# POWER.net
KiCad netlist of a schematic drawn in Altium Designer
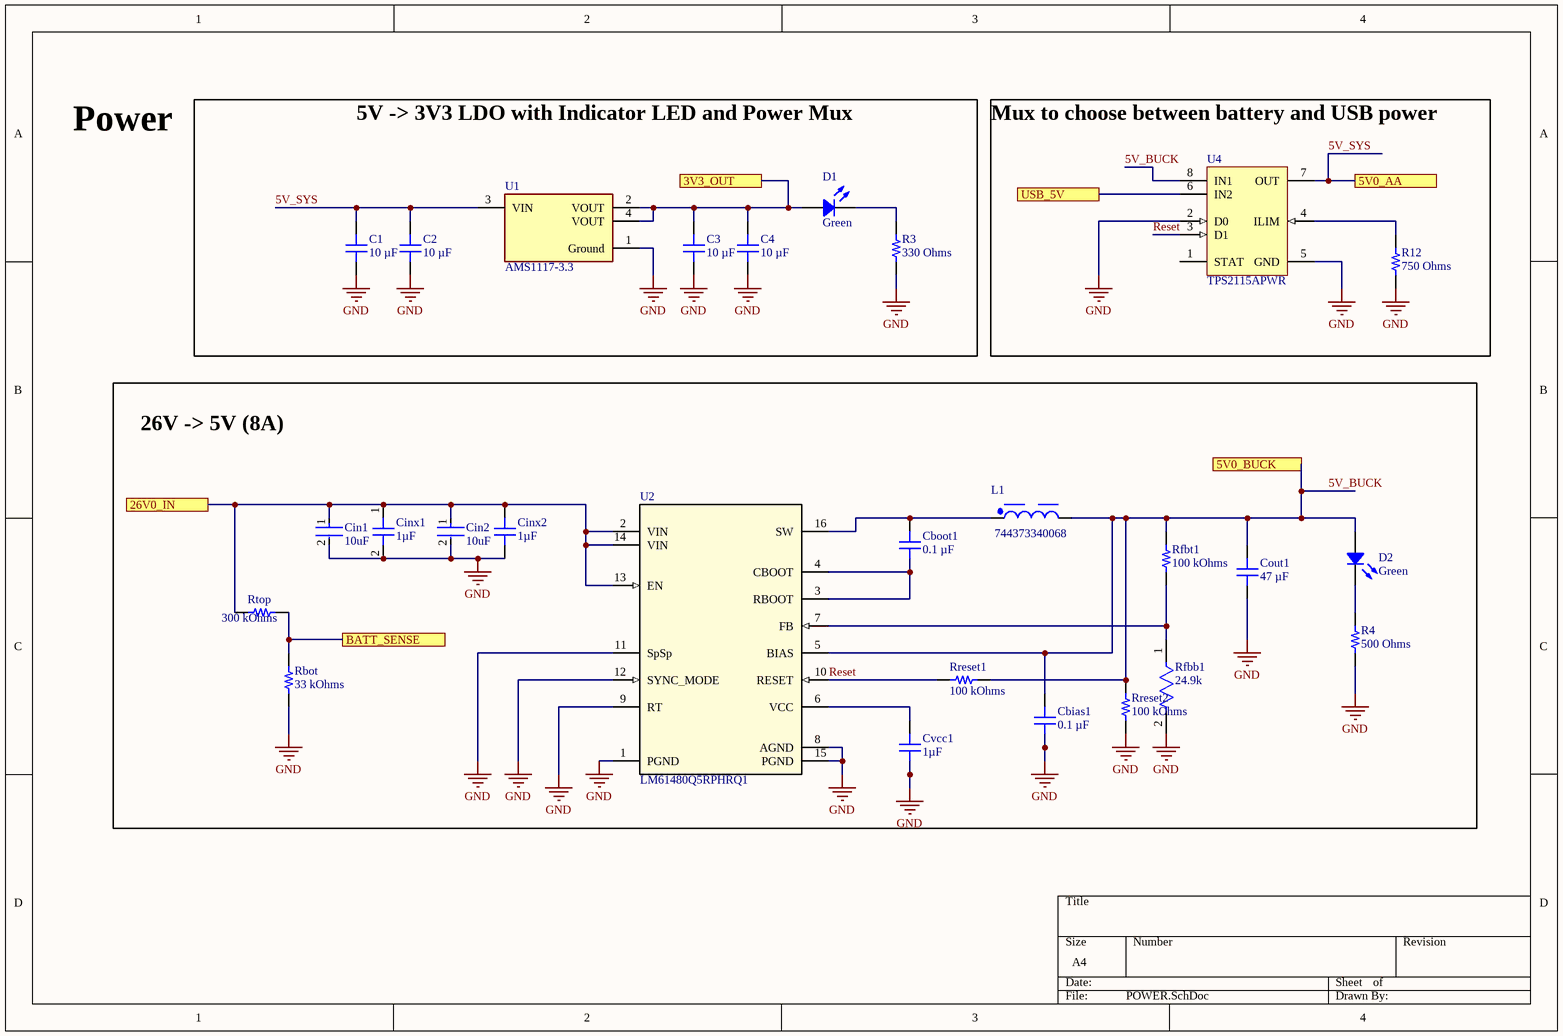
[diagram p0: POWER.SchDoc]

(export (version "E")
  (design (tool "Eeschema 10.0.6"))
  (components
    (comp (ref "C1")
      (value "10 µF")
      (footprint "CAP 0603_1608")
      (description "0603 X5R 10UF10% 16V")
      (fields (field (name "PART NUMBER") "CM105X5R106K16AT") (field (name "MANUFACTURER") "KYOCERA AVX"))
      (libsource (lib "Celestial Altium Library - altium_library") (part "Capacitor"))
    )
    (comp (ref "C2")
      (value "10 µF")
      (footprint "CAP 0603_1608")
      (description "0603 X5R 10UF10% 16V")
      (fields (field (name "PART NUMBER") "CM105X5R106K16AT") (field (name "MANUFACTURER") "KYOCERA AVX"))
      (libsource (lib "Celestial Altium Library - altium_library") (part "Capacitor"))
    )
    (comp (ref "C3")
      (value "10 µF")
      (footprint "CAP 0603_1608")
      (description "0603 X5R 10UF10% 16V")
      (fields (field (name "PART NUMBER") "CM105X5R106K16AT") (field (name "MANUFACTURER") "KYOCERA AVX"))
      (libsource (lib "Celestial Altium Library - altium_library") (part "Capacitor"))
    )
    (comp (ref "C4")
      (value "10 µF")
      (footprint "CAP 0603_1608")
      (description "0603 X5R 10UF10% 16V")
      (fields (field (name "PART NUMBER") "CM105X5R106K16AT") (field (name "MANUFACTURER") "KYOCERA AVX"))
      (libsource (lib "Celestial Altium Library - altium_library") (part "Capacitor"))
    )
    (comp (ref "Cbias1")
      (value "0.1 µF")
      (footprint "CAP 0603_1608")
      (description "CAP CER 0.1UF 50V X7R 0603")
      (fields
        (field (name "PART NUMBER") "C0603C104K5RAC7411")
        (field (name "CAPACITANCE") "0.1 µF")
        (field (name "MANUFACTURER") "KEMET")
      )
      (libsource (lib "Celestial Altium Library - altium_library") (part "Capacitor"))
    )
    (comp (ref "Cboot1")
      (value "0.1 µF")
      (footprint "CAP 0603_1608")
      (description "CAP CER 0.1UF 50V X7R 0603")
      (fields
        (field (name "PART NUMBER") "C0603C104K5RAC7411")
        (field (name "CAPACITANCE") "0.1 µF")
        (field (name "MANUFACTURER") "KEMET")
      )
      (libsource (lib "Celestial Altium Library - altium_library") (part "Capacitor"))
    )
    (comp (ref "Cin1")
      (value "10uF")
      (footprint "FP-GRT31C-0_2-IPC_A")
      (description "CAP CER 10UF 50V X5R 1206")
      (fields (field (name "TOLERANCE") "20%"))
      (libsource (lib "Altium Content Vault") (part "11868f565c42a9108669ba33697ecf6"))
    )
    (comp (ref "Cin2")
      (value "10uF")
      (footprint "FP-GRT31C-0_2-IPC_A")
      (description "CAP CER 10UF 50V X5R 1206")
      (fields (field (name "TOLERANCE") "20%"))
      (libsource (lib "Altium Content Vault") (part "11868f565c42a9108669ba33697ecf6"))
    )
    (comp (ref "Cinx1")
      (value "1µF")
      (footprint "CAP 0603_1608")
      (description "CAP CER 1UF 50V X5R 0603")
      (fields
        (field (name "PART NUMBER") "06035D105MAT2A")
        (field (name "CAPACITANCE") "1µF")
        (field (name "MANUFACTURER") "AVX Corporation")
      )
      (libsource (lib "") (part "Capacitor_1"))
    )
    (comp (ref "Cinx2")
      (value "1µF")
      (footprint "CAP 0603_1608")
      (description "CAP CER 1UF 50V X5R 0603")
      (fields
        (field (name "PART NUMBER") "06035D105MAT2A")
        (field (name "CAPACITANCE") "1µF")
        (field (name "MANUFACTURER") "AVX Corporation")
      )
      (libsource (lib "Celestial Altium Library - altium_library") (part "Capacitor"))
    )
    (comp (ref "Cout1")
      (value "47 µF")
      (footprint "CAP 0603_1608")
      (description "CAP CER 47UF 6.3V X5R 0603")
      (fields
        (field (name "PART NUMBER") "CL10A476MQ8QRNC")
        (field (name "CAPACITANCE") "47 µF")
        (field (name "MANUFACTURER") "Samsung Electro-Mechanics")
      )
      (libsource (lib "Celestial Altium Library - altium_library") (part "Capacitor"))
    )
    (comp (ref "Cvcc1")
      (value "1µF")
      (footprint "CAP 0603_1608")
      (description "CAP CER 1UF 50V X5R 0603")
      (fields
        (field (name "PART NUMBER") "06035D105MAT2A")
        (field (name "CAPACITANCE") "1µF")
        (field (name "MANUFACTURER") "AVX Corporation")
      )
      (libsource (lib "Celestial Altium Library - altium_library") (part "Capacitor"))
    )
    (comp (ref "D1")
      (value "Green")
      (footprint "LED 0603_1608 GREEN")
      (description "LED GREEN CLEAR 0603 SMD")
      (fields (field (name "PART NUMBER") "150060GS75003") (field (name "MANUFACTURER") "Würth Elektronik"))
      (libsource (lib "Celestial Altium Library - altium_library") (part "LED"))
    )
    (comp (ref "D2")
      (value "Green")
      (footprint "LED 0603_1608 GREEN")
      (description "LED GREEN CLEAR 0603 SMD")
      (fields (field (name "PART NUMBER") "150060GS75003") (field (name "MANUFACTURER") "Würth Elektronik"))
      (libsource (lib "Celestial Altium Library - altium_library") (part "LED"))
    )
    (comp (ref "L1")
      (value "744373340068")
      (footprint "WE-LHMI_5020")
      (description "We-lhmi Series, Shielded Wire-wound SMD Inductor 680 Nh +/-20% Wire-wound 6.8A I")
      (fields (field (name "TOLERANCE") "20%"))
      (libsource (lib "Altium Content Vault") (part "Inductor - 2"))
    )
    (comp (ref "R3")
      (value "330 Ohms")
      (footprint "RES 0603_1608")
      (description "RES 330 OHM 0.1% 1/8W 0603")
      (fields
        (field (name "PART NUMBER") "ERA-3VEB3300V")
        (field (name "MANUFACTURER") "Panasonic Electronic Components")
      )
      (libsource (lib "Celestial Altium Library - altium_library") (part "Resistor"))
    )
    (comp (ref "R4")
      (value "500 Ohms")
      (footprint "RES 1206_3216")
      (description "RES SMD 500 OHM 0.05% 0.4W 1206")
      (fields
        (field (name "PART NUMBER") "PLT1206Z5000AST5")
        (field (name "MANUFACTURER") "Vishay Thin Film")
      )
      (libsource (lib "Celestial Altium Library - altium_library") (part "Resistor"))
    )
    (comp (ref "R12")
      (value "750 Ohms")
      (footprint "RES 0603_1608")
      (description "RES SMD 750 OHM 1% 1/16W 0603")
      (fields
        (field (name "PART NUMBER") "CPF0603F750RC1")
        (field (name "MANUFACTURER") "TE Connectivity Passive Product")
      )
      (libsource (lib "Celestial Altium Library - altium_library") (part "Resistor"))
    )
    (comp (ref "Rbot")
      (value "33 kOhms")
      (footprint "YAGEO RES 0603_1608")
      (description "RES SMD 33K OHM 1% 1/10W 0603")
      (fields (field (name "PART NUMBER") "RT0603FRE0733KL") (field (name "MANUFACTURER") "Yageo"))
      (libsource (lib "Celestial Altium Library - altium_library") (part "Resistor"))
    )
    (comp (ref "Rfbb1")
      (value "24.9k")
      (footprint "FP-TFCR0603-IPC_A")
      (description "RES Thin Film,  24.9kΩ, 1%, 0.1W, 50ppm/°C, 0603")
      (libsource (lib "Altium Content Vault") (part "1029c3af85768c4190bb7ad29bc67b5"))
    )
    (comp (ref "Rfbt1")
      (value "100 kOhms")
      (footprint "RES 0603_1608")
      (description "RES 100K OHM 0.1% 1/16W 0603")
      (fields
        (field (name "PART NUMBER") "RNCS0603BKE100K")
        (field (name "MANUFACTURER") "Stackpole Electronics Inc")
      )
      (libsource (lib "Celestial Altium Library - altium_library") (part "Resistor"))
    )
    (comp (ref "Rreset1")
      (value "100 kOhms")
      (footprint "RES 0603_1608")
      (description "RES 100K OHM 0.1% 1/16W 0603")
      (fields
        (field (name "PART NUMBER") "RNCS0603BKE100K")
        (field (name "MANUFACTURER") "Stackpole Electronics Inc")
      )
      (libsource (lib "Celestial Altium Library - altium_library") (part "Resistor"))
    )
    (comp (ref "Rreset2")
      (value "100 kOhms")
      (footprint "RES 0603_1608")
      (description "RES 100K OHM 0.1% 1/16W 0603")
      (fields
        (field (name "PART NUMBER") "RNCS0603BKE100K")
        (field (name "MANUFACTURER") "Stackpole Electronics Inc")
      )
      (libsource (lib "Celestial Altium Library - altium_library") (part "Resistor"))
    )
    (comp (ref "Rtop")
      (value "300 kOhms")
      (footprint "YAGEO RES 0603_1608")
      (description "RES 300K OHM 1% 1/10W 0603")
      (fields (field (name "PART NUMBER") "RC0603FR-07300KL") (field (name "MANUFACTURER") "Yageo"))
      (libsource (lib "Celestial Altium Library - altium_library") (part "Resistor"))
    )
    (comp (ref "U1")
      (value "AMS1117-3.3")
      (footprint "FP-AMS1117-IPC_C")
      (description "LDO Voltage Regulators 1A, 3.3V")
      (fields
        (field (name "OCTOPART") "https://octopart.com/ams1117-3.3-advanced+monolithic+systems-25899300")
        (field (name "MANUFACTURER") "Advanced Monolithic Systems")
      )
      (libsource (lib "Altium Content Vault") (part "8bdbb5f8e77002000e30dd2845d0354"))
    )
    (comp (ref "U2")
      (value "LM61480Q5RPHRQ1")
      (footprint "RPH0016A")
      (description "Automotive 8A buck converter optimized for power density and low EMI 16-VQFN-HR -40 to 150")
      (fields (field (name "COPYRIGHT") "Copyright (C) 2025 Ultra Librarian. All rights reserved."))
      (libsource (lib "LM61480Q5RPHRQ1") (part "LM61480Q5RPHRQ1"))
    )
    (comp (ref "U4")
      (value "TPS2115APWR")
      (footprint "PW0008A_N")
      (fields (field (name "MANUFACTURER") "Texas Instruments"))
      (libsource (lib "Altium Content Vault") (part "TI-TPS2115APW8"))
    )
  )
  (nets
    (net (code "1") (name "/3V3_OUT") (class "Default")
      (node (ref "C3") (pin "2") (pinfunction "2_2") (pintype "passive"))
      (node (ref "C4") (pin "2") (pinfunction "2_2") (pintype "passive"))
      (node (ref "D1") (pin "1") (pinfunction "1_1") (pintype "passive"))
      (node (ref "U1") (pin "2") (pinfunction "VOUT_2") (pintype "passive"))
      (node (ref "U1") (pin "4") (pinfunction "VOUT_4") (pintype "passive"))
    )
    (net (code "2") (name "/5V_BUCK") (class "Default")
      (node (ref "Cbias1") (pin "1") (pinfunction "1_1") (pintype "passive"))
      (node (ref "Cout1") (pin "1") (pinfunction "1_1") (pintype "passive"))
      (node (ref "D2") (pin "1") (pinfunction "1_1") (pintype "passive"))
      (node (ref "L1") (pin "2") (pinfunction "2_2") (pintype "passive"))
      (node (ref "Rfbt1") (pin "1") (pinfunction "1_1") (pintype "passive"))
      (node (ref "Rreset1") (pin "2") (pinfunction "2_2") (pintype "passive"))
      (node (ref "Rreset2") (pin "1") (pinfunction "1_1") (pintype "passive"))
      (node (ref "U2") (pin "5") (pinfunction "BIAS_5") (pintype "passive"))
      (node (ref "U4") (pin "8") (pinfunction "IN1_8") (pintype "power_in"))
    )
    (net (code "3") (name "/5V_SYS") (class "Default")
      (node (ref "C1") (pin "2") (pinfunction "2_2") (pintype "passive"))
      (node (ref "C2") (pin "2") (pinfunction "2_2") (pintype "passive"))
      (node (ref "U1") (pin "3") (pinfunction "VIN_3") (pintype "power_in"))
      (node (ref "U4") (pin "7") (pinfunction "OUT_7") (pintype "power_in"))
    )
    (net (code "4") (name "/26V0_IN") (class "Default")
      (node (ref "Cin1") (pin "1") (pinfunction "1_1") (pintype "passive"))
      (node (ref "Cin2") (pin "1") (pinfunction "1_1") (pintype "passive"))
      (node (ref "Cinx1") (pin "1") (pinfunction "1_1") (pintype "passive"))
      (node (ref "Cinx2") (pin "1") (pinfunction "1_1") (pintype "passive"))
      (node (ref "Rtop") (pin "1") (pinfunction "1_1") (pintype "passive"))
      (node (ref "U2") (pin "13") (pinfunction "EN_13") (pintype "input"))
      (node (ref "U2") (pin "14") (pinfunction "VIN_14") (pintype "power_in"))
      (node (ref "U2") (pin "2") (pinfunction "VIN_2") (pintype "power_in"))
    )
    (net (code "5") (name "/BATT_SENSE") (class "Default")
      (node (ref "Rbot") (pin "1") (pinfunction "1_1") (pintype "passive"))
      (node (ref "Rtop") (pin "2") (pinfunction "2_2") (pintype "passive"))
    )
    (net (code "6") (name "/Reset") (class "Default")
      (node (ref "Rreset1") (pin "1") (pinfunction "1_1") (pintype "passive"))
      (node (ref "U2") (pin "10") (pinfunction "RESET_10") (pintype "input"))
      (node (ref "U4") (pin "3") (pinfunction "D1_3") (pintype "input"))
    )
    (net (code "7") (name "/USB_5V") (class "Default")
      (node (ref "U4") (pin "6") (pinfunction "IN2_6") (pintype "power_in"))
    )
    (net (code "8") (name "GND") (class "Default")
      (node (ref "C1") (pin "1") (pinfunction "1_1") (pintype "passive"))
      (node (ref "C2") (pin "1") (pinfunction "1_1") (pintype "passive"))
      (node (ref "C3") (pin "1") (pinfunction "1_1") (pintype "passive"))
      (node (ref "C4") (pin "1") (pinfunction "1_1") (pintype "passive"))
      (node (ref "Cbias1") (pin "2") (pinfunction "2_2") (pintype "passive"))
      (node (ref "Cin1") (pin "2") (pinfunction "2_2") (pintype "passive"))
      (node (ref "Cin2") (pin "2") (pinfunction "2_2") (pintype "passive"))
      (node (ref "Cinx1") (pin "2") (pinfunction "2_2") (pintype "passive"))
      (node (ref "Cinx2") (pin "2") (pinfunction "2_2") (pintype "passive"))
      (node (ref "Cout1") (pin "2") (pinfunction "2_2") (pintype "passive"))
      (node (ref "Cvcc1") (pin "2") (pinfunction "2_2") (pintype "passive"))
      (node (ref "R12") (pin "2") (pinfunction "2_2") (pintype "passive"))
      (node (ref "R3") (pin "1") (pinfunction "1_1") (pintype "passive"))
      (node (ref "R4") (pin "2") (pinfunction "2_2") (pintype "passive"))
      (node (ref "Rbot") (pin "2") (pinfunction "2_2") (pintype "passive"))
      (node (ref "Rfbb1") (pin "2") (pinfunction "2_2") (pintype "passive"))
      (node (ref "Rreset2") (pin "2") (pinfunction "2_2") (pintype "passive"))
      (node (ref "U1") (pin "1") (pinfunction "Ground_1") (pintype "power_in"))
      (node (ref "U2") (pin "1") (pinfunction "PGND_1") (pintype "power_in"))
      (node (ref "U2") (pin "11") (pinfunction "SpSp_11") (pintype "passive"))
      (node (ref "U2") (pin "12") (pinfunction "SYNC_MODE_12") (pintype "input"))
      (node (ref "U2") (pin "15") (pinfunction "PGND_15") (pintype "power_in"))
      (node (ref "U2") (pin "8") (pinfunction "AGND_8") (pintype "power_in"))
      (node (ref "U2") (pin "9") (pinfunction "RT_9") (pintype "passive"))
      (node (ref "U4") (pin "2") (pinfunction "D0_2") (pintype "input"))
      (node (ref "U4") (pin "5") (pinfunction "GND_5") (pintype "power_in"))
    )
    (net (code "9") (name "Net-(D1-Pad2)") (class "Default")
      (node (ref "D1") (pin "2") (pinfunction "2_2") (pintype "passive"))
      (node (ref "R3") (pin "2") (pinfunction "2_2") (pintype "passive"))
    )
    (net (code "10") (name "Net-(D2-Pad2)") (class "Default")
      (node (ref "D2") (pin "2") (pinfunction "2_2") (pintype "passive"))
      (node (ref "R4") (pin "1") (pinfunction "1_1") (pintype "passive"))
    )
    (net (code "11") (name "Net-(U2-CBOOT)") (class "Default")
      (node (ref "Cboot1") (pin "2") (pinfunction "2_2") (pintype "passive"))
      (node (ref "U2") (pin "3") (pinfunction "RBOOT_3") (pintype "passive"))
      (node (ref "U2") (pin "4") (pinfunction "CBOOT_4") (pintype "passive"))
    )
    (net (code "12") (name "Net-(U2-FB)") (class "Default")
      (node (ref "Rfbb1") (pin "1") (pinfunction "1_1") (pintype "passive"))
      (node (ref "Rfbt1") (pin "2") (pinfunction "2_2") (pintype "passive"))
      (node (ref "U2") (pin "7") (pinfunction "FB_7") (pintype "input"))
    )
    (net (code "13") (name "Net-(U2-SW)") (class "Default")
      (node (ref "Cboot1") (pin "1") (pinfunction "1_1") (pintype "passive"))
      (node (ref "L1") (pin "1") (pinfunction "1_1") (pintype "passive"))
      (node (ref "U2") (pin "16") (pinfunction "SW_16") (pintype "power_in"))
    )
    (net (code "14") (name "Net-(U2-VCC)") (class "Default")
      (node (ref "Cvcc1") (pin "1") (pinfunction "1_1") (pintype "passive"))
      (node (ref "U2") (pin "6") (pinfunction "VCC_6") (pintype "power_in"))
    )
    (net (code "15") (name "Net-(U4-ILIM)") (class "Default")
      (node (ref "R12") (pin "1") (pinfunction "1_1") (pintype "passive"))
      (node (ref "U4") (pin "4") (pinfunction "ILIM_4") (pintype "input"))
    )
    (net (code "16") (name "unconnected-(U4-STAT-Pad1)") (class "Default")
      (node (ref "U4") (pin "1") (pinfunction "STAT_1") (pintype "tri_state"))
    )
  )
)
